# TXV2.net
KiCad netlist of a schematic drawn in EAGLE
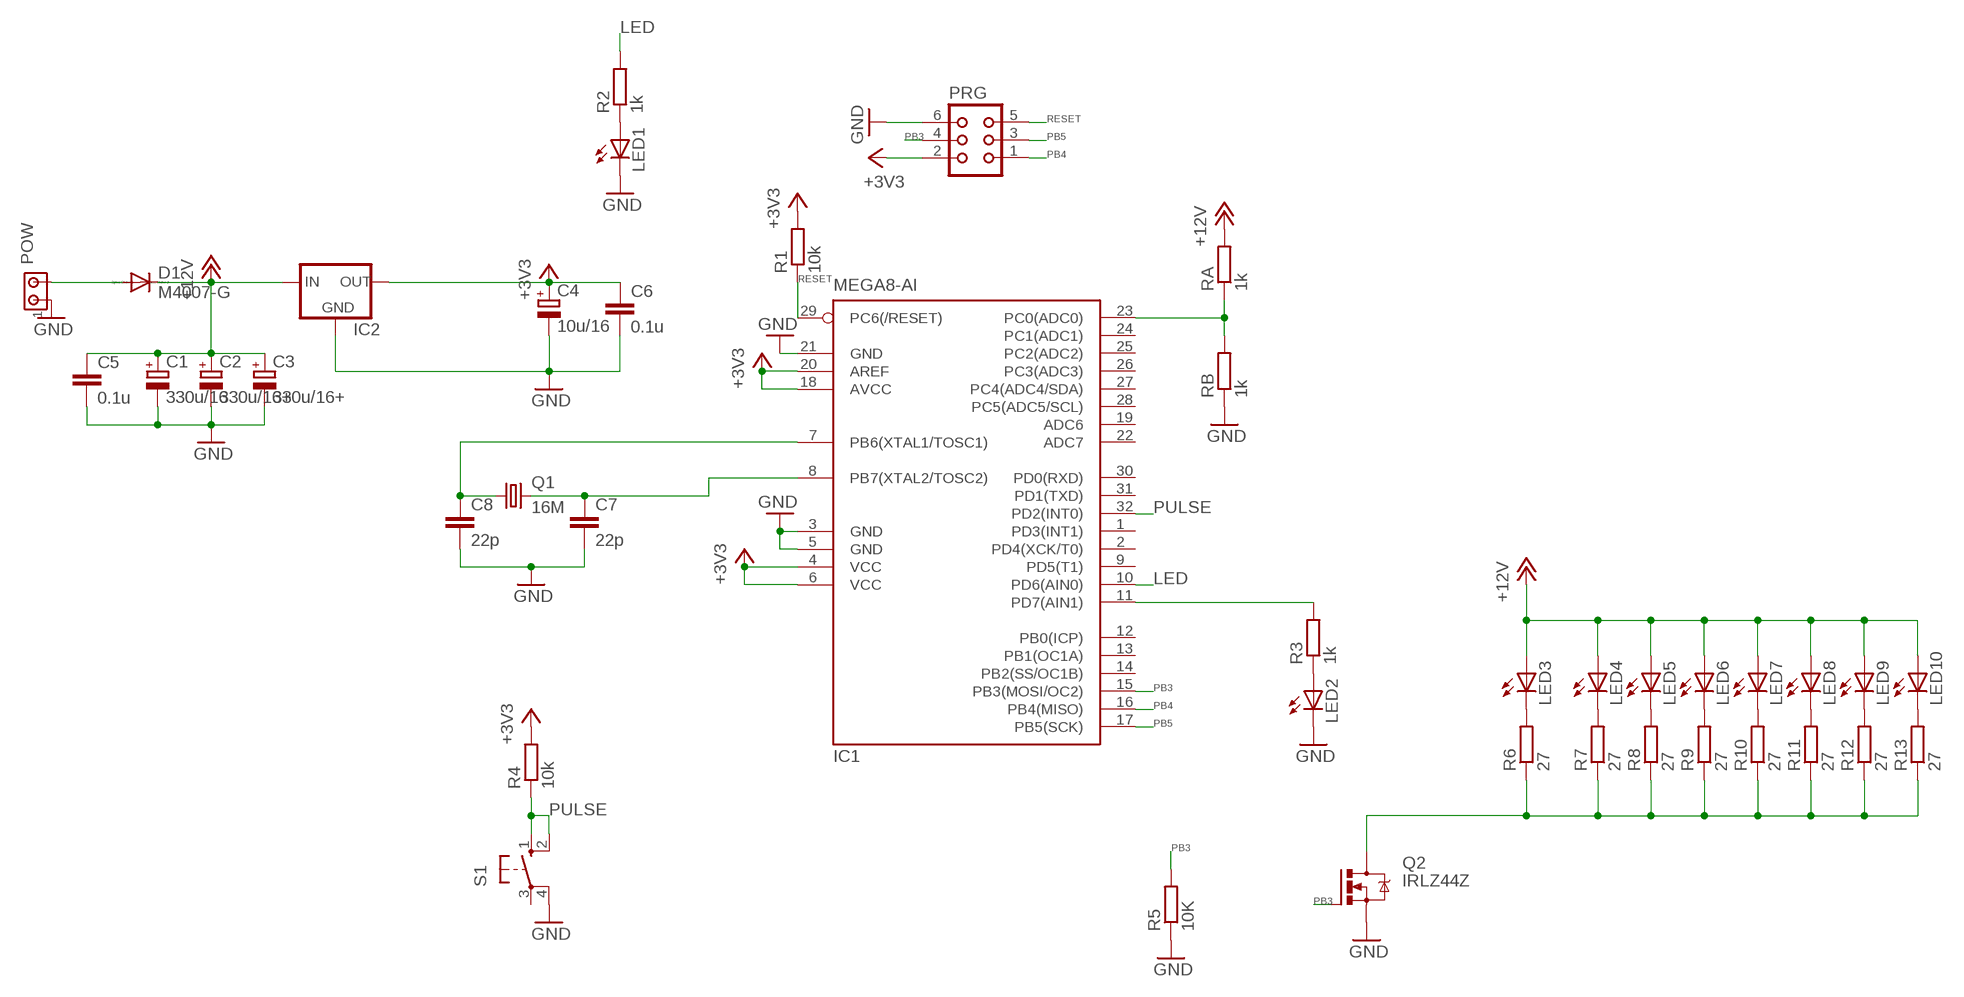
[diagram p0: schematic, sheet 1]

(export (version "E")
  (design (tool "Eeschema 10.0.6"))
  (components
    (comp (ref "C1")
      (value "330u/16")
      (footprint "eagle-import:E2,5-7")
      (libsource (lib "eagle-import") (part "CPOL-EUE2.5-7"))
    )
    (comp (ref "C2")
      (value "330u/16+")
      (footprint "eagle-import:E2,5-7")
      (libsource (lib "eagle-import") (part "CPOL-EUE2.5-7"))
    )
    (comp (ref "C3")
      (value "330u/16+")
      (footprint "eagle-import:E2,5-7")
      (libsource (lib "eagle-import") (part "CPOL-EUE2.5-7"))
    )
    (comp (ref "C4")
      (value "10u/16")
      (footprint "eagle-import:E2,5-6")
      (libsource (lib "eagle-import") (part "CPOL-EUE2.5-6"))
    )
    (comp (ref "C5")
      (value "0.1u")
      (footprint "eagle-import:C0402")
      (libsource (lib "eagle-import") (part "C-EUC0402"))
    )
    (comp (ref "C6")
      (value "0.1u")
      (footprint "eagle-import:C0402")
      (libsource (lib "eagle-import") (part "C-EUC0402"))
    )
    (comp (ref "C7")
      (value "22p")
      (footprint "eagle-import:C0805")
      (libsource (lib "eagle-import") (part "C-EUC0805"))
    )
    (comp (ref "C8")
      (value "22p")
      (footprint "eagle-import:C0805")
      (libsource (lib "eagle-import") (part "C-EUC0805"))
    )
    (comp (ref "D1")
      (value "M4007-G")
      (footprint "eagle-import:SOD-123_MINI-SMA")
      (libsource (lib "eagle-import") (part "CGRM400-G7"))
    )
    (comp (ref "IC1")
      (value "MEGA8-AI")
      (footprint "eagle-import:TQFP32-08")
      (fields (field (name "MPN") "ATMEGA8-16AU"))
      (libsource (lib "eagle-import") (part "MEGA8-AI"))
    )
    (comp (ref "IC2")
      (value "78LXX")
      (footprint "eagle-import:78LXX")
      (libsource (lib "eagle-import") (part "78LXX"))
    )
    (comp (ref "LED1")
      (value "LED5MM")
      (footprint "eagle-import:LED5MM")
      (libsource (lib "eagle-import") (part "LED5MM"))
    )
    (comp (ref "LED2")
      (value "LED5MM")
      (footprint "eagle-import:LED5MM")
      (libsource (lib "eagle-import") (part "LED5MM"))
    )
    (comp (ref "LED3")
      (value "LED5MM")
      (footprint "eagle-import:LED5MM")
      (libsource (lib "eagle-import") (part "LED5MM"))
    )
    (comp (ref "LED4")
      (value "LED5MM")
      (footprint "eagle-import:LED5MM")
      (libsource (lib "eagle-import") (part "LED5MM"))
    )
    (comp (ref "LED5")
      (value "LED5MM")
      (footprint "eagle-import:LED5MM")
      (libsource (lib "eagle-import") (part "LED5MM"))
    )
    (comp (ref "LED6")
      (value "LED5MM")
      (footprint "eagle-import:LED5MM")
      (libsource (lib "eagle-import") (part "LED5MM"))
    )
    (comp (ref "LED7")
      (value "LED5MM")
      (footprint "eagle-import:LED5MM")
      (libsource (lib "eagle-import") (part "LED5MM"))
    )
    (comp (ref "LED8")
      (value "LED5MM")
      (footprint "eagle-import:LED5MM")
      (libsource (lib "eagle-import") (part "LED5MM"))
    )
    (comp (ref "LED9")
      (value "LED5MM")
      (footprint "eagle-import:LED5MM")
      (libsource (lib "eagle-import") (part "LED5MM"))
    )
    (comp (ref "LED10")
      (value "LED5MM")
      (footprint "eagle-import:LED5MM")
      (libsource (lib "eagle-import") (part "LED5MM"))
    )
    (comp (ref "POW")
      (value "MTA02-100")
      (footprint "eagle-import:10X02MTA")
      (libsource (lib "eagle-import") (part "MTA02-100"))
    )
    (comp (ref "PRG")
      (value "CON06")
      (footprint "eagle-import:CON06")
      (libsource (lib "eagle-import") (part "CON06"))
    )
    (comp (ref "Q1")
      (value "16M")
      (footprint "eagle-import:HC49UP")
      (libsource (lib "eagle-import") (part "CRYSTALHC49UP"))
    )
    (comp (ref "Q2")
      (value "IRLZ44Z")
      (footprint "eagle-import:TO220BH")
      (libsource (lib "eagle-import") (part "IRLZ44Z"))
    )
    (comp (ref "R1")
      (value "10k")
      (footprint "eagle-import:M1206")
      (libsource (lib "eagle-import") (part "R-EU_M1206"))
    )
    (comp (ref "R2")
      (value "1k")
      (footprint "eagle-import:M1206")
      (libsource (lib "eagle-import") (part "R-EU_M1206"))
    )
    (comp (ref "R3")
      (value "1k")
      (footprint "eagle-import:M1206")
      (libsource (lib "eagle-import") (part "R-EU_M1206"))
    )
    (comp (ref "R4")
      (value "10k")
      (footprint "eagle-import:M1206")
      (libsource (lib "eagle-import") (part "R-EU_M1206"))
    )
    (comp (ref "R5")
      (value "10K")
      (footprint "eagle-import:M1206")
      (libsource (lib "eagle-import") (part "R-EU_M1206"))
    )
    (comp (ref "R6")
      (value "27")
      (footprint "eagle-import:0204_7")
      (libsource (lib "eagle-import") (part "R-EU_0204/7"))
    )
    (comp (ref "R7")
      (value "27")
      (footprint "eagle-import:0204_7")
      (libsource (lib "eagle-import") (part "R-EU_0204/7"))
    )
    (comp (ref "R8")
      (value "27")
      (footprint "eagle-import:0204_7")
      (libsource (lib "eagle-import") (part "R-EU_0204/7"))
    )
    (comp (ref "R9")
      (value "27")
      (footprint "eagle-import:0204_7")
      (libsource (lib "eagle-import") (part "R-EU_0204/7"))
    )
    (comp (ref "R10")
      (value "27")
      (footprint "eagle-import:0204_7")
      (libsource (lib "eagle-import") (part "R-EU_0204/7"))
    )
    (comp (ref "R11")
      (value "27")
      (footprint "eagle-import:0204_7")
      (libsource (lib "eagle-import") (part "R-EU_0204/7"))
    )
    (comp (ref "R12")
      (value "27")
      (footprint "eagle-import:0204_7")
      (libsource (lib "eagle-import") (part "R-EU_0204/7"))
    )
    (comp (ref "R13")
      (value "27")
      (footprint "eagle-import:0204_7")
      (libsource (lib "eagle-import") (part "R-EU_0204/7"))
    )
    (comp (ref "RA")
      (value "1k")
      (footprint "eagle-import:M1206")
      (libsource (lib "eagle-import") (part "R-EU_M1206"))
    )
    (comp (ref "RB")
      (value "1k")
      (footprint "eagle-import:M1206")
      (libsource (lib "eagle-import") (part "R-EU_M1206"))
    )
    (comp (ref "S1")
      (value "10-XX")
      (footprint "eagle-import:B3F-10XX")
      (fields (field (name "MPN") "B3F-1000"))
      (libsource (lib "eagle-import") (part "10-XX"))
    )
  )
  (nets
    (net (code "1") (name "+3V3") (class "Default")
      (node (ref "C4") (pin "+") (pinfunction "+_+") (pintype "passive"))
      (node (ref "C6") (pin "1") (pinfunction "1_1") (pintype "passive"))
      (node (ref "IC1") (pin "18") (pinfunction "AVCC_18") (pintype "power_in"))
      (node (ref "IC1") (pin "20") (pinfunction "AREF_20") (pintype "passive"))
      (node (ref "IC1") (pin "4") (pinfunction "VCC_4") (pintype "power_in"))
      (node (ref "IC1") (pin "6") (pinfunction "VCC_6") (pintype "power_in"))
      (node (ref "IC2") (pin "OUT") (pinfunction "OUT_OUT") (pintype "passive"))
      (node (ref "PRG") (pin "2") (pinfunction "2_2") (pintype "passive"))
      (node (ref "R1") (pin "2") (pinfunction "2_2") (pintype "passive"))
      (node (ref "R4") (pin "2") (pinfunction "2_2") (pintype "passive"))
    )
    (net (code "2") (name "+12V") (class "Default")
      (node (ref "C1") (pin "+") (pinfunction "+_+") (pintype "passive"))
      (node (ref "C2") (pin "+") (pinfunction "+_+") (pintype "passive"))
      (node (ref "C3") (pin "+") (pinfunction "+_+") (pintype "passive"))
      (node (ref "C5") (pin "1") (pinfunction "1_1") (pintype "passive"))
      (node (ref "D1") (pin "C") (pinfunction "C_C") (pintype "passive"))
      (node (ref "IC2") (pin "IN") (pinfunction "IN_IN") (pintype "input"))
      (node (ref "LED10") (pin "A") (pinfunction "A_A") (pintype "passive"))
      (node (ref "LED3") (pin "A") (pinfunction "A_A") (pintype "passive"))
      (node (ref "LED4") (pin "A") (pinfunction "A_A") (pintype "passive"))
      (node (ref "LED5") (pin "A") (pinfunction "A_A") (pintype "passive"))
      (node (ref "LED6") (pin "A") (pinfunction "A_A") (pintype "passive"))
      (node (ref "LED7") (pin "A") (pinfunction "A_A") (pintype "passive"))
      (node (ref "LED8") (pin "A") (pinfunction "A_A") (pintype "passive"))
      (node (ref "LED9") (pin "A") (pinfunction "A_A") (pintype "passive"))
      (node (ref "RA") (pin "2") (pinfunction "2_2") (pintype "passive"))
    )
    (net (code "3") (name "/LED") (class "Default")
      (node (ref "IC1") (pin "10") (pinfunction "PD6(AIN0)_10") (pintype "bidirectional"))
      (node (ref "R2") (pin "2") (pinfunction "2_2") (pintype "passive"))
    )
    (net (code "4") (name "/PB3") (class "Default")
      (node (ref "IC1") (pin "15") (pinfunction "PB3(MOSI/OC2)_15") (pintype "bidirectional"))
      (node (ref "PRG") (pin "4") (pinfunction "4_4") (pintype "passive"))
      (node (ref "Q2") (pin "G") (pinfunction "G_G") (pintype "passive"))
      (node (ref "R5") (pin "2") (pinfunction "2_2") (pintype "passive"))
    )
    (net (code "5") (name "/PB4") (class "Default")
      (node (ref "IC1") (pin "16") (pinfunction "PB4(MISO)_16") (pintype "bidirectional"))
      (node (ref "PRG") (pin "1") (pinfunction "1_1") (pintype "passive"))
    )
    (net (code "6") (name "/PB5") (class "Default")
      (node (ref "IC1") (pin "17") (pinfunction "PB5(SCK)_17") (pintype "bidirectional"))
      (node (ref "PRG") (pin "3") (pinfunction "3_3") (pintype "passive"))
    )
    (net (code "7") (name "/PULSE") (class "Default")
      (node (ref "IC1") (pin "32") (pinfunction "PD2(INT0)_32") (pintype "bidirectional"))
      (node (ref "R4") (pin "1") (pinfunction "1_1") (pintype "passive"))
      (node (ref "S1") (pin "1") (pinfunction "S_1") (pintype "passive"))
      (node (ref "S1") (pin "2") (pinfunction "S1_2") (pintype "passive"))
    )
    (net (code "8") (name "/RESET") (class "Default")
      (node (ref "IC1") (pin "29") (pinfunction "PC6(/RESET)_29") (pintype "bidirectional"))
      (node (ref "PRG") (pin "5") (pinfunction "5_5") (pintype "passive"))
      (node (ref "R1") (pin "1") (pinfunction "1_1") (pintype "passive"))
    )
    (net (code "9") (name "GND") (class "Default")
      (node (ref "C1") (pin "-") (pinfunction "-_-") (pintype "passive"))
      (node (ref "C2") (pin "-") (pinfunction "-_-") (pintype "passive"))
      (node (ref "C3") (pin "-") (pinfunction "-_-") (pintype "passive"))
      (node (ref "C4") (pin "-") (pinfunction "-_-") (pintype "passive"))
      (node (ref "C5") (pin "2") (pinfunction "2_2") (pintype "passive"))
      (node (ref "C6") (pin "2") (pinfunction "2_2") (pintype "passive"))
      (node (ref "C7") (pin "2") (pinfunction "2_2") (pintype "passive"))
      (node (ref "C8") (pin "2") (pinfunction "2_2") (pintype "passive"))
      (node (ref "IC1") (pin "21") (pinfunction "GND_21") (pintype "power_in"))
      (node (ref "IC1") (pin "3") (pinfunction "GND_3") (pintype "power_in"))
      (node (ref "IC1") (pin "5") (pinfunction "GND_5") (pintype "power_in"))
      (node (ref "IC2") (pin "GND") (pinfunction "GND_GND") (pintype "input"))
      (node (ref "LED1") (pin "K") (pinfunction "C_K") (pintype "passive"))
      (node (ref "LED2") (pin "K") (pinfunction "C_K") (pintype "passive"))
      (node (ref "POW") (pin "1") (pinfunction "1_1") (pintype "passive"))
      (node (ref "PRG") (pin "6") (pinfunction "6_6") (pintype "passive"))
      (node (ref "Q2") (pin "S") (pinfunction "S_S") (pintype "passive"))
      (node (ref "R5") (pin "1") (pinfunction "1_1") (pintype "passive"))
      (node (ref "RB") (pin "1") (pinfunction "1_1") (pintype "passive"))
      (node (ref "S1") (pin "4") (pinfunction "P1_4") (pintype "passive"))
    )
    (net (code "10") (name "Net-(D1-PadA)") (class "Default")
      (node (ref "D1") (pin "A") (pinfunction "A_A") (pintype "passive"))
      (node (ref "POW") (pin "2") (pinfunction "2_2") (pintype "passive"))
    )
    (net (code "11") (name "Net-(IC1-PB6(XTAL1{slash}TOSC1))") (class "Default")
      (node (ref "C8") (pin "1") (pinfunction "1_1") (pintype "passive"))
      (node (ref "IC1") (pin "7") (pinfunction "PB6(XTAL1/TOSC1)_7") (pintype "bidirectional"))
      (node (ref "Q1") (pin "1") (pinfunction "1_1") (pintype "passive"))
    )
    (net (code "12") (name "Net-(IC1-PB7(XTAL2{slash}TOSC2))") (class "Default")
      (node (ref "C7") (pin "1") (pinfunction "1_1") (pintype "passive"))
      (node (ref "IC1") (pin "8") (pinfunction "PB7(XTAL2/TOSC2)_8") (pintype "bidirectional"))
      (node (ref "Q1") (pin "2") (pinfunction "2_2") (pintype "passive"))
    )
    (net (code "13") (name "Net-(IC1-PC0(ADC0))") (class "Default")
      (node (ref "IC1") (pin "23") (pinfunction "PC0(ADC0)_23") (pintype "bidirectional"))
      (node (ref "RA") (pin "1") (pinfunction "1_1") (pintype "passive"))
      (node (ref "RB") (pin "2") (pinfunction "2_2") (pintype "passive"))
    )
    (net (code "14") (name "Net-(IC1-PD7(AIN1))") (class "Default")
      (node (ref "IC1") (pin "11") (pinfunction "PD7(AIN1)_11") (pintype "bidirectional"))
      (node (ref "R3") (pin "2") (pinfunction "2_2") (pintype "passive"))
    )
    (net (code "15") (name "Net-(LED1-PadA)") (class "Default")
      (node (ref "LED1") (pin "A") (pinfunction "A_A") (pintype "passive"))
      (node (ref "R2") (pin "1") (pinfunction "1_1") (pintype "passive"))
    )
    (net (code "16") (name "Net-(LED2-PadA)") (class "Default")
      (node (ref "LED2") (pin "A") (pinfunction "A_A") (pintype "passive"))
      (node (ref "R3") (pin "1") (pinfunction "1_1") (pintype "passive"))
    )
    (net (code "17") (name "Net-(LED3-C)") (class "Default")
      (node (ref "LED3") (pin "K") (pinfunction "C_K") (pintype "passive"))
      (node (ref "R6") (pin "2") (pinfunction "2_2") (pintype "passive"))
    )
    (net (code "18") (name "Net-(LED4-C)") (class "Default")
      (node (ref "LED4") (pin "K") (pinfunction "C_K") (pintype "passive"))
      (node (ref "R7") (pin "2") (pinfunction "2_2") (pintype "passive"))
    )
    (net (code "19") (name "Net-(LED5-C)") (class "Default")
      (node (ref "LED5") (pin "K") (pinfunction "C_K") (pintype "passive"))
      (node (ref "R8") (pin "2") (pinfunction "2_2") (pintype "passive"))
    )
    (net (code "20") (name "Net-(LED6-C)") (class "Default")
      (node (ref "LED6") (pin "K") (pinfunction "C_K") (pintype "passive"))
      (node (ref "R9") (pin "2") (pinfunction "2_2") (pintype "passive"))
    )
    (net (code "21") (name "Net-(LED7-C)") (class "Default")
      (node (ref "LED7") (pin "K") (pinfunction "C_K") (pintype "passive"))
      (node (ref "R10") (pin "2") (pinfunction "2_2") (pintype "passive"))
    )
    (net (code "22") (name "Net-(LED8-C)") (class "Default")
      (node (ref "LED8") (pin "K") (pinfunction "C_K") (pintype "passive"))
      (node (ref "R11") (pin "2") (pinfunction "2_2") (pintype "passive"))
    )
    (net (code "23") (name "Net-(LED9-C)") (class "Default")
      (node (ref "LED9") (pin "K") (pinfunction "C_K") (pintype "passive"))
      (node (ref "R12") (pin "2") (pinfunction "2_2") (pintype "passive"))
    )
    (net (code "24") (name "Net-(LED10-C)") (class "Default")
      (node (ref "LED10") (pin "K") (pinfunction "C_K") (pintype "passive"))
      (node (ref "R13") (pin "2") (pinfunction "2_2") (pintype "passive"))
    )
    (net (code "25") (name "Net-(Q2-PadD)") (class "Default")
      (node (ref "Q2") (pin "D") (pinfunction "D_D") (pintype "passive"))
      (node (ref "R10") (pin "1") (pinfunction "1_1") (pintype "passive"))
      (node (ref "R11") (pin "1") (pinfunction "1_1") (pintype "passive"))
      (node (ref "R12") (pin "1") (pinfunction "1_1") (pintype "passive"))
      (node (ref "R13") (pin "1") (pinfunction "1_1") (pintype "passive"))
      (node (ref "R6") (pin "1") (pinfunction "1_1") (pintype "passive"))
      (node (ref "R7") (pin "1") (pinfunction "1_1") (pintype "passive"))
      (node (ref "R8") (pin "1") (pinfunction "1_1") (pintype "passive"))
      (node (ref "R9") (pin "1") (pinfunction "1_1") (pintype "passive"))
    )
    (net (code "26") (name "unconnected-(IC1-ADC6-Pad19)") (class "Default")
      (node (ref "IC1") (pin "19") (pinfunction "ADC6_19") (pintype "bidirectional"))
    )
    (net (code "27") (name "unconnected-(IC1-ADC7-Pad22)") (class "Default")
      (node (ref "IC1") (pin "22") (pinfunction "ADC7_22") (pintype "bidirectional"))
    )
    (net (code "28") (name "unconnected-(IC1-PB0(ICP)-Pad12)") (class "Default")
      (node (ref "IC1") (pin "12") (pinfunction "PB0(ICP)_12") (pintype "bidirectional"))
    )
    (net (code "29") (name "unconnected-(IC1-PB1(OC1A)-Pad13)") (class "Default")
      (node (ref "IC1") (pin "13") (pinfunction "PB1(OC1A)_13") (pintype "bidirectional"))
    )
    (net (code "30") (name "unconnected-(IC1-PB2(SS{slash}OC1B)-Pad14)") (class "Default")
      (node (ref "IC1") (pin "14") (pinfunction "PB2(SS/OC1B)_14") (pintype "bidirectional"))
    )
    (net (code "31") (name "unconnected-(IC1-PC1(ADC1)-Pad24)") (class "Default")
      (node (ref "IC1") (pin "24") (pinfunction "PC1(ADC1)_24") (pintype "bidirectional"))
    )
    (net (code "32") (name "unconnected-(IC1-PC2(ADC2)-Pad25)") (class "Default")
      (node (ref "IC1") (pin "25") (pinfunction "PC2(ADC2)_25") (pintype "bidirectional"))
    )
    (net (code "33") (name "unconnected-(IC1-PC3(ADC3)-Pad26)") (class "Default")
      (node (ref "IC1") (pin "26") (pinfunction "PC3(ADC3)_26") (pintype "bidirectional"))
    )
    (net (code "34") (name "unconnected-(IC1-PC4(ADC4{slash}SDA)-Pad27)") (class "Default")
      (node (ref "IC1") (pin "27") (pinfunction "PC4(ADC4/SDA)_27") (pintype "bidirectional"))
    )
    (net (code "35") (name "unconnected-(IC1-PC5(ADC5{slash}SCL)-Pad28)") (class "Default")
      (node (ref "IC1") (pin "28") (pinfunction "PC5(ADC5/SCL)_28") (pintype "bidirectional"))
    )
    (net (code "36") (name "unconnected-(IC1-PD0(RXD)-Pad30)") (class "Default")
      (node (ref "IC1") (pin "30") (pinfunction "PD0(RXD)_30") (pintype "bidirectional"))
    )
    (net (code "37") (name "unconnected-(IC1-PD1(TXD)-Pad31)") (class "Default")
      (node (ref "IC1") (pin "31") (pinfunction "PD1(TXD)_31") (pintype "bidirectional"))
    )
    (net (code "38") (name "unconnected-(IC1-PD3(INT1)-Pad1)") (class "Default")
      (node (ref "IC1") (pin "1") (pinfunction "PD3(INT1)_1") (pintype "bidirectional"))
    )
    (net (code "39") (name "unconnected-(IC1-PD4(XCK{slash}T0)-Pad2)") (class "Default")
      (node (ref "IC1") (pin "2") (pinfunction "PD4(XCK/T0)_2") (pintype "bidirectional"))
    )
    (net (code "40") (name "unconnected-(IC1-PD5(T1)-Pad9)") (class "Default")
      (node (ref "IC1") (pin "9") (pinfunction "PD5(T1)_9") (pintype "bidirectional"))
    )
    (net (code "41") (name "unconnected-(S1-P-Pad3)") (class "Default")
      (node (ref "S1") (pin "3") (pinfunction "P_3") (pintype "passive"))
    )
  )
)
